# sensor.net
KiCad netlist of a schematic drawn in EAGLE
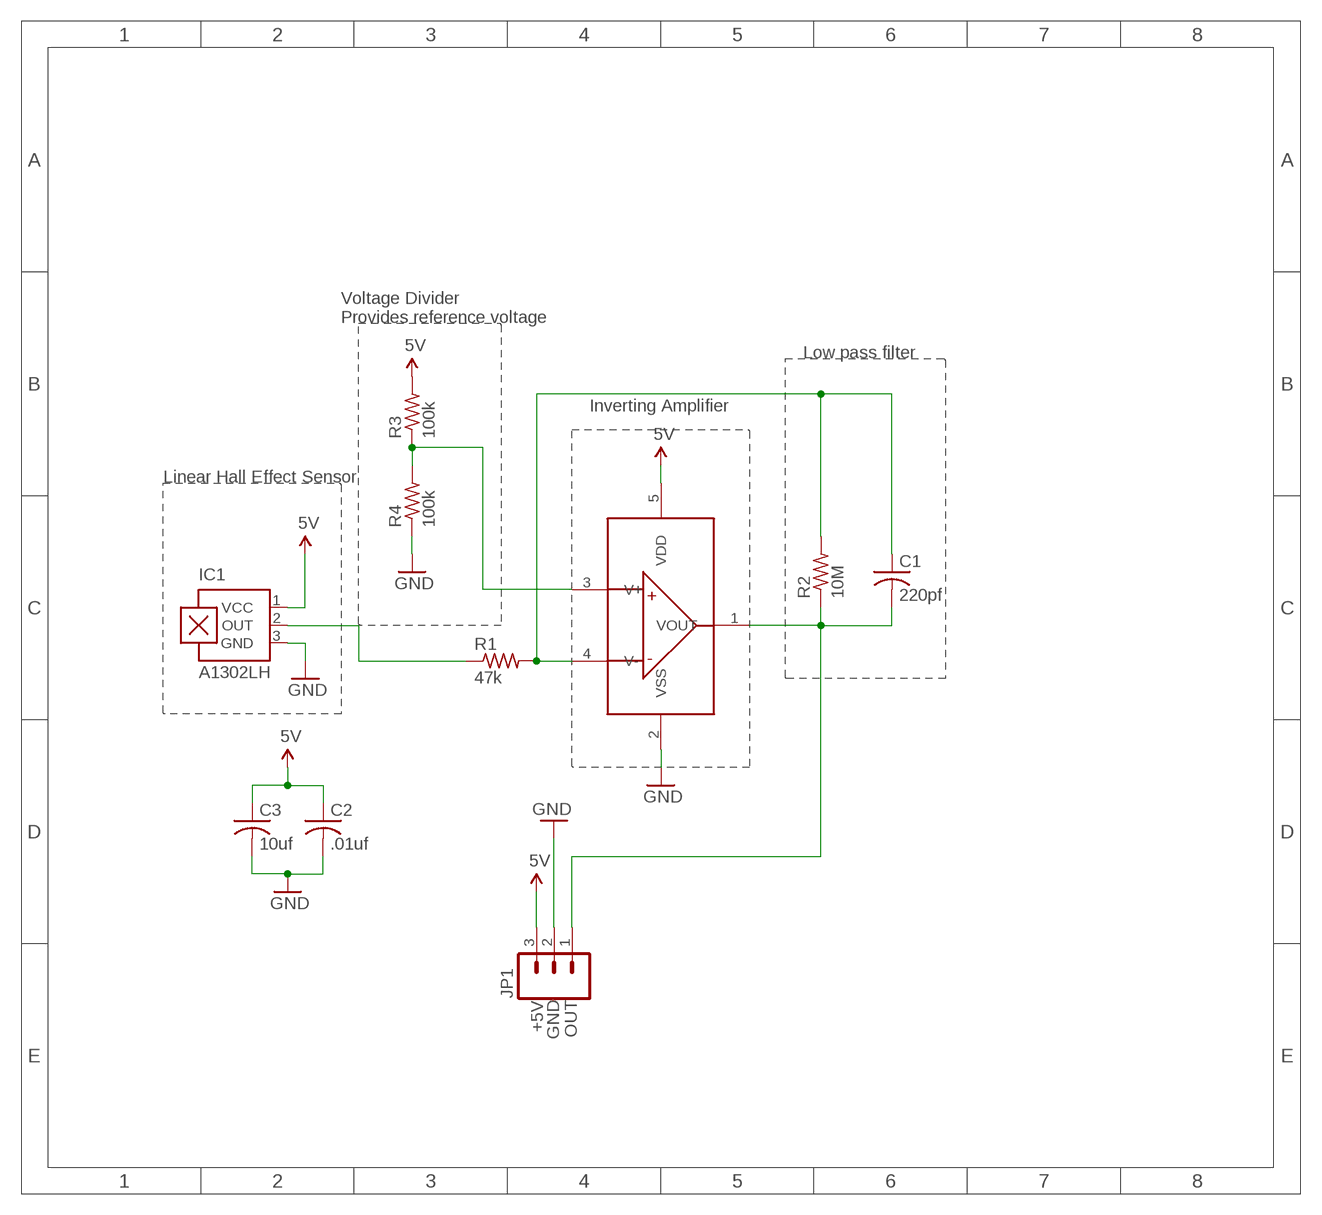
[diagram p0: schematic, sheet 1]

(export (version "E")
  (design (tool "Eeschema 10.0.6"))
  (components
    (comp (ref "C1")
      (value "220pf")
      (footprint "eagle-import:C0805")
      (libsource (lib "eagle-import") (part "C-USC0805"))
    )
    (comp (ref "C2")
      (value ".01uf")
      (footprint "eagle-import:C0805")
      (libsource (lib "eagle-import") (part "C-USC0805"))
    )
    (comp (ref "C3")
      (value "10uf")
      (footprint "eagle-import:C0805")
      (libsource (lib "eagle-import") (part "C-USC0805"))
    )
    (comp (ref "IC1")
      (value "A1302LH")
      (footprint "eagle-import:SOT23-W")
      (fields (field (name "MF") "ALLEGRO MICROSYSTEMS, INC.") (field (name "MPN") "A1302ELHLT-T"))
      (libsource (lib "eagle-import") (part "A13?LH02"))
    )
    (comp (ref "JP1")
      (value "M03PTH")
      (footprint "eagle-import:1X03")
      (libsource (lib "eagle-import") (part "M03PTH"))
    )
    (comp (ref "R1")
      (value "47k")
      (footprint "eagle-import:R0805")
      (libsource (lib "eagle-import") (part "R-US_R0805"))
    )
    (comp (ref "R2")
      (value "10M")
      (footprint "eagle-import:R0805")
      (libsource (lib "eagle-import") (part "R-US_R0805"))
    )
    (comp (ref "R3")
      (value "100k")
      (footprint "eagle-import:R0805")
      (libsource (lib "eagle-import") (part "R-US_R0805"))
    )
    (comp (ref "R4")
      (value "100k")
      (footprint "eagle-import:R0805")
      (libsource (lib "eagle-import") (part "R-US_R0805"))
    )
    (comp (ref "U$1")
      (value "MCP601")
      (footprint "eagle-import:SOT23-5")
      (libsource (lib "eagle-import") (part "MCP601"))
    )
  )
  (nets
    (net (code "1") (name "5V") (class "Default")
      (node (ref "C2") (pin "1") (pinfunction "1_1") (pintype "passive"))
      (node (ref "C3") (pin "1") (pinfunction "1_1") (pintype "passive"))
      (node (ref "IC1") (pin "1") (pinfunction "VCC_1") (pintype "power_in"))
      (node (ref "JP1") (pin "3") (pinfunction "3_3") (pintype "passive"))
      (node (ref "R3") (pin "2") (pinfunction "2_2") (pintype "passive"))
      (node (ref "U$1") (pin "5") (pinfunction "VDD_5") (pintype "power_in"))
    )
    (net (code "2") (name "GND") (class "Default")
      (node (ref "C2") (pin "2") (pinfunction "2_2") (pintype "passive"))
      (node (ref "C3") (pin "2") (pinfunction "2_2") (pintype "passive"))
      (node (ref "IC1") (pin "3") (pinfunction "GND_3") (pintype "power_in"))
      (node (ref "JP1") (pin "2") (pinfunction "2_2") (pintype "passive"))
      (node (ref "R4") (pin "1") (pinfunction "1_1") (pintype "passive"))
      (node (ref "U$1") (pin "2") (pinfunction "VSS_2") (pintype "power_in"))
    )
    (net (code "3") (name "Net-(IC1-OUT)") (class "Default")
      (node (ref "IC1") (pin "2") (pinfunction "OUT_2") (pintype "output"))
      (node (ref "R1") (pin "1") (pinfunction "1_1") (pintype "passive"))
    )
    (net (code "4") (name "Net-(U$1-V+)") (class "Default")
      (node (ref "R3") (pin "1") (pinfunction "1_1") (pintype "passive"))
      (node (ref "R4") (pin "2") (pinfunction "2_2") (pintype "passive"))
      (node (ref "U$1") (pin "3") (pinfunction "V+_3") (pintype "input"))
    )
    (net (code "5") (name "Net-(U$1-V-)") (class "Default")
      (node (ref "C1") (pin "1") (pinfunction "1_1") (pintype "passive"))
      (node (ref "R1") (pin "2") (pinfunction "2_2") (pintype "passive"))
      (node (ref "R2") (pin "2") (pinfunction "2_2") (pintype "passive"))
      (node (ref "U$1") (pin "4") (pinfunction "V-_4") (pintype "input"))
    )
    (net (code "6") (name "Net-(U$1-VOUT)") (class "Default")
      (node (ref "C1") (pin "2") (pinfunction "2_2") (pintype "passive"))
      (node (ref "JP1") (pin "1") (pinfunction "1_1") (pintype "passive"))
      (node (ref "R2") (pin "1") (pinfunction "1_1") (pintype "passive"))
      (node (ref "U$1") (pin "1") (pinfunction "VOUT_1") (pintype "output"))
    )
  )
)
